# 02_-_SCHEMATIC.net
KiCad netlist of a schematic drawn in Altium Designer
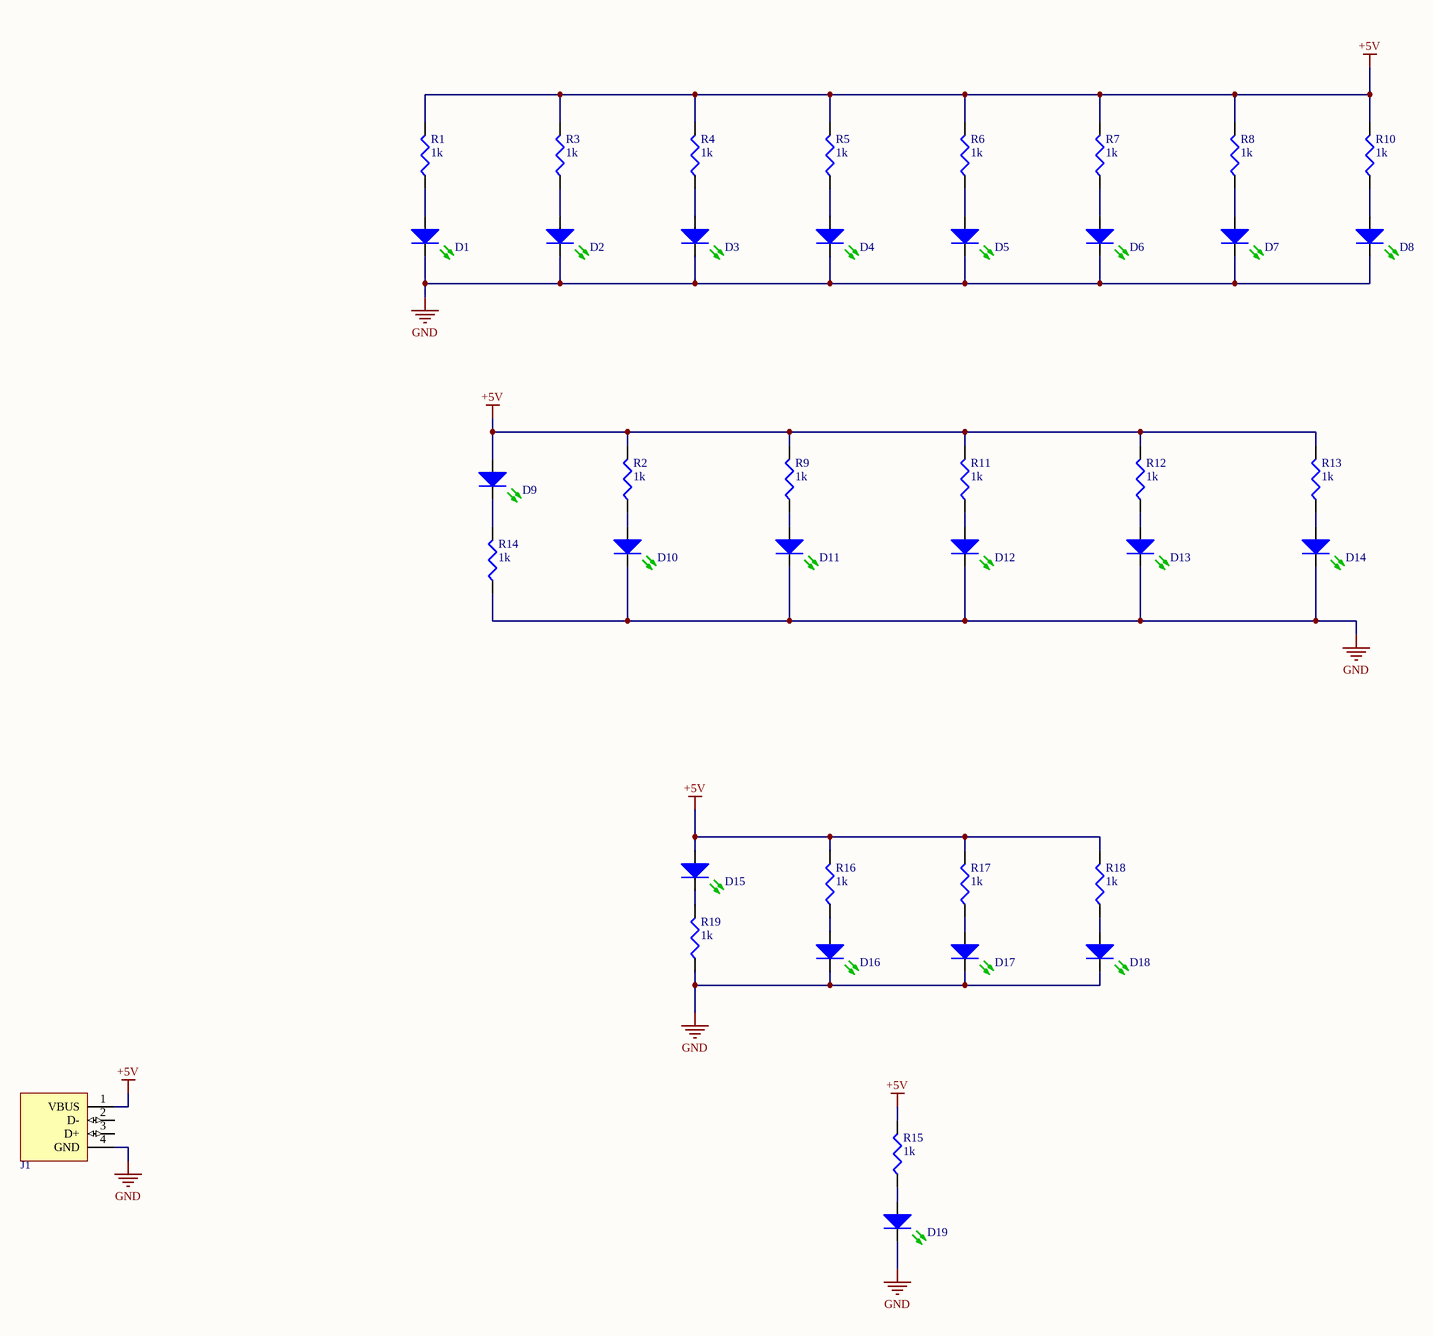
[diagram p0: [02] - SCHEMATIC.SchDoc]

(export (version "E")
  (design (tool "Eeschema 10.0.6"))
  (components
    (comp (ref "D1")
      (value "FYL-3014PGC1A")
      (footprint "LED_THT_Type_3mm_GREEN")
      (description "LED, THT 3mm, Green")
      (fields (field (name "MANUFACTURER") "FORYARD"))
      (libsource (lib "psblib") (part "LED_GREEN_THT_3MM"))
    )
    (comp (ref "D2")
      (value "FYL-3014PGC1A")
      (footprint "LED_THT_Type_3mm_GREEN")
      (description "LED, THT 3mm, Green")
      (fields (field (name "MANUFACTURER") "FORYARD"))
      (libsource (lib "psblib") (part "LED_GREEN_THT_3MM"))
    )
    (comp (ref "D3")
      (value "FYL-3014PGC1A")
      (footprint "LED_THT_Type_3mm_GREEN")
      (description "LED, THT 3mm, Green")
      (fields (field (name "MANUFACTURER") "FORYARD"))
      (libsource (lib "psblib") (part "LED_GREEN_THT_3MM"))
    )
    (comp (ref "D4")
      (value "FYL-3014PGC1A")
      (footprint "LED_THT_Type_3mm_GREEN")
      (description "LED, THT 3mm, Green")
      (fields (field (name "MANUFACTURER") "FORYARD"))
      (libsource (lib "psblib") (part "LED_GREEN_THT_3MM"))
    )
    (comp (ref "D5")
      (value "FYL-3014PGC1A")
      (footprint "LED_THT_Type_3mm_GREEN")
      (description "LED, THT 3mm, Green")
      (fields (field (name "MANUFACTURER") "FORYARD"))
      (libsource (lib "psblib") (part "LED_GREEN_THT_3MM"))
    )
    (comp (ref "D6")
      (value "FYL-3014PGC1A")
      (footprint "LED_THT_Type_3mm_GREEN")
      (description "LED, THT 3mm, Green")
      (fields (field (name "MANUFACTURER") "FORYARD"))
      (libsource (lib "psblib") (part "LED_GREEN_THT_3MM"))
    )
    (comp (ref "D7")
      (value "FYL-3014PGC1A")
      (footprint "LED_THT_Type_3mm_GREEN")
      (description "LED, THT 3mm, Green")
      (fields (field (name "MANUFACTURER") "FORYARD"))
      (libsource (lib "psblib") (part "LED_GREEN_THT_3MM"))
    )
    (comp (ref "D8")
      (value "FYL-3014PGC1A")
      (footprint "LED_THT_Type_3mm_GREEN")
      (description "LED, THT 3mm, Green")
      (fields (field (name "MANUFACTURER") "FORYARD"))
      (libsource (lib "psblib") (part "LED_GREEN_THT_3MM"))
    )
    (comp (ref "D9")
      (value "FYL-3014PGC1A")
      (footprint "LED_THT_Type_3mm_GREEN")
      (description "LED, THT 3mm, Green")
      (fields (field (name "MANUFACTURER") "FORYARD"))
      (libsource (lib "psblib") (part "LED_GREEN_THT_3MM"))
    )
    (comp (ref "D10")
      (value "FYL-3014PGC1A")
      (footprint "LED_THT_Type_3mm_GREEN")
      (description "LED, THT 3mm, Green")
      (fields (field (name "MANUFACTURER") "FORYARD"))
      (libsource (lib "psblib") (part "LED_GREEN_THT_3MM"))
    )
    (comp (ref "D11")
      (value "FYL-3014PGC1A")
      (footprint "LED_THT_Type_3mm_GREEN")
      (description "LED, THT 3mm, Green")
      (fields (field (name "MANUFACTURER") "FORYARD"))
      (libsource (lib "psblib") (part "LED_GREEN_THT_3MM"))
    )
    (comp (ref "D12")
      (value "FYL-3014PGC1A")
      (footprint "LED_THT_Type_3mm_GREEN")
      (description "LED, THT 3mm, Green")
      (fields (field (name "MANUFACTURER") "FORYARD"))
      (libsource (lib "psblib") (part "LED_GREEN_THT_3MM"))
    )
    (comp (ref "D13")
      (value "FYL-3014PGC1A")
      (footprint "LED_THT_Type_3mm_GREEN")
      (description "LED, THT 3mm, Green")
      (fields (field (name "MANUFACTURER") "FORYARD"))
      (libsource (lib "psblib") (part "LED_GREEN_THT_3MM"))
    )
    (comp (ref "D14")
      (value "FYL-3014PGC1A")
      (footprint "LED_THT_Type_3mm_GREEN")
      (description "LED, THT 3mm, Green")
      (fields (field (name "MANUFACTURER") "FORYARD"))
      (libsource (lib "psblib") (part "LED_GREEN_THT_3MM"))
    )
    (comp (ref "D15")
      (value "FYL-3014PGC1A")
      (footprint "LED_THT_Type_3mm_GREEN")
      (description "LED, THT 3mm, Green")
      (fields (field (name "MANUFACTURER") "FORYARD"))
      (libsource (lib "psblib") (part "LED_GREEN_THT_3MM"))
    )
    (comp (ref "D16")
      (value "FYL-3014PGC1A")
      (footprint "LED_THT_Type_3mm_GREEN")
      (description "LED, THT 3mm, Green")
      (fields (field (name "MANUFACTURER") "FORYARD"))
      (libsource (lib "psblib") (part "LED_GREEN_THT_3MM"))
    )
    (comp (ref "D17")
      (value "FYL-3014PGC1A")
      (footprint "LED_THT_Type_3mm_GREEN")
      (description "LED, THT 3mm, Green")
      (fields (field (name "MANUFACTURER") "FORYARD"))
      (libsource (lib "psblib") (part "LED_GREEN_THT_3MM"))
    )
    (comp (ref "D18")
      (value "FYL-3014PGC1A")
      (footprint "LED_THT_Type_3mm_GREEN")
      (description "LED, THT 3mm, Green")
      (fields (field (name "MANUFACTURER") "FORYARD"))
      (libsource (lib "psblib") (part "LED_GREEN_THT_3MM"))
    )
    (comp (ref "D19")
      (value "FYL-3014PGC1A")
      (footprint "LED_THT_Type_3mm_GREEN")
      (description "LED, THT 3mm, Green")
      (fields (field (name "MANUFACTURER") "FORYARD"))
      (libsource (lib "psblib") (part "LED_GREEN_THT_3MM"))
    )
    (comp (ref "J1")
      (value "USB_A_PCB")
      (footprint "USB-A-PCB")
      (description "USB A PCB Edge connector")
      (libsource (lib "psblib") (part "USB_A_PCB"))
    )
    (comp (ref "R1")
      (value "1k")
      (footprint "R0603")
      (description "RES, 1k, 1%, 0.063 W, 0603")
      (fields
        (field (name "TOLERANCE") "±1%")
        (field (name ".CHECKED PCB") "OK RF")
        (field (name ".CHECKED SCH") "RF")
      )
      (libsource (lib "psblib") (part "R0603-1k"))
    )
    (comp (ref "R2")
      (value "1k")
      (footprint "R0603")
      (description "RES, 1k, 1%, 0.063 W, 0603")
      (fields
        (field (name "TOLERANCE") "±1%")
        (field (name ".CHECKED PCB") "OK RF")
        (field (name ".CHECKED SCH") "RF")
      )
      (libsource (lib "psblib") (part "R0603-1k"))
    )
    (comp (ref "R3")
      (value "1k")
      (footprint "R0603")
      (description "RES, 1k, 1%, 0.063 W, 0603")
      (fields
        (field (name "TOLERANCE") "±1%")
        (field (name ".CHECKED PCB") "OK RF")
        (field (name ".CHECKED SCH") "RF")
      )
      (libsource (lib "psblib") (part "R0603-1k"))
    )
    (comp (ref "R4")
      (value "1k")
      (footprint "R0603")
      (description "RES, 1k, 1%, 0.063 W, 0603")
      (fields
        (field (name "TOLERANCE") "±1%")
        (field (name ".CHECKED PCB") "OK RF")
        (field (name ".CHECKED SCH") "RF")
      )
      (libsource (lib "psblib") (part "R0603-1k"))
    )
    (comp (ref "R5")
      (value "1k")
      (footprint "R0603")
      (description "RES, 1k, 1%, 0.063 W, 0603")
      (fields
        (field (name "TOLERANCE") "±1%")
        (field (name ".CHECKED PCB") "OK RF")
        (field (name ".CHECKED SCH") "RF")
      )
      (libsource (lib "psblib") (part "R0603-1k"))
    )
    (comp (ref "R6")
      (value "1k")
      (footprint "R0603")
      (description "RES, 1k, 1%, 0.063 W, 0603")
      (fields
        (field (name "TOLERANCE") "±1%")
        (field (name ".CHECKED PCB") "OK RF")
        (field (name ".CHECKED SCH") "RF")
      )
      (libsource (lib "psblib") (part "R0603-1k"))
    )
    (comp (ref "R7")
      (value "1k")
      (footprint "R0603")
      (description "RES, 1k, 1%, 0.063 W, 0603")
      (fields
        (field (name "TOLERANCE") "±1%")
        (field (name ".CHECKED PCB") "OK RF")
        (field (name ".CHECKED SCH") "RF")
      )
      (libsource (lib "psblib") (part "R0603-1k"))
    )
    (comp (ref "R8")
      (value "1k")
      (footprint "R0603")
      (description "RES, 1k, 1%, 0.063 W, 0603")
      (fields
        (field (name "TOLERANCE") "±1%")
        (field (name ".CHECKED PCB") "OK RF")
        (field (name ".CHECKED SCH") "RF")
      )
      (libsource (lib "psblib") (part "R0603-1k"))
    )
    (comp (ref "R9")
      (value "1k")
      (footprint "R0603")
      (description "RES, 1k, 1%, 0.063 W, 0603")
      (fields
        (field (name "TOLERANCE") "±1%")
        (field (name ".CHECKED PCB") "OK RF")
        (field (name ".CHECKED SCH") "RF")
      )
      (libsource (lib "psblib") (part "R0603-1k"))
    )
    (comp (ref "R10")
      (value "1k")
      (footprint "R0603")
      (description "RES, 1k, 1%, 0.063 W, 0603")
      (fields
        (field (name "TOLERANCE") "±1%")
        (field (name ".CHECKED PCB") "OK RF")
        (field (name ".CHECKED SCH") "RF")
      )
      (libsource (lib "psblib") (part "R0603-1k"))
    )
    (comp (ref "R11")
      (value "1k")
      (footprint "R0603")
      (description "RES, 1k, 1%, 0.063 W, 0603")
      (fields
        (field (name "TOLERANCE") "±1%")
        (field (name ".CHECKED PCB") "OK RF")
        (field (name ".CHECKED SCH") "RF")
      )
      (libsource (lib "psblib") (part "R0603-1k"))
    )
    (comp (ref "R12")
      (value "1k")
      (footprint "R0603")
      (description "RES, 1k, 1%, 0.063 W, 0603")
      (fields
        (field (name "TOLERANCE") "±1%")
        (field (name ".CHECKED PCB") "OK RF")
        (field (name ".CHECKED SCH") "RF")
      )
      (libsource (lib "psblib") (part "R0603-1k"))
    )
    (comp (ref "R13")
      (value "1k")
      (footprint "R0603")
      (description "RES, 1k, 1%, 0.063 W, 0603")
      (fields
        (field (name "TOLERANCE") "±1%")
        (field (name ".CHECKED PCB") "OK RF")
        (field (name ".CHECKED SCH") "RF")
      )
      (libsource (lib "psblib") (part "R0603-1k"))
    )
    (comp (ref "R14")
      (value "1k")
      (footprint "R0603")
      (description "RES, 1k, 1%, 0.063 W, 0603")
      (fields
        (field (name "TOLERANCE") "±1%")
        (field (name ".CHECKED PCB") "OK RF")
        (field (name ".CHECKED SCH") "RF")
      )
      (libsource (lib "psblib") (part "R0603-1k"))
    )
    (comp (ref "R15")
      (value "1k")
      (footprint "R0603")
      (description "RES, 1k, 1%, 0.063 W, 0603")
      (fields
        (field (name "TOLERANCE") "±1%")
        (field (name ".CHECKED PCB") "OK RF")
        (field (name ".CHECKED SCH") "RF")
      )
      (libsource (lib "psblib") (part "R0603-1k"))
    )
    (comp (ref "R16")
      (value "1k")
      (footprint "R0603")
      (description "RES, 1k, 1%, 0.063 W, 0603")
      (fields
        (field (name "TOLERANCE") "±1%")
        (field (name ".CHECKED PCB") "OK RF")
        (field (name ".CHECKED SCH") "RF")
      )
      (libsource (lib "psblib") (part "R0603-1k"))
    )
    (comp (ref "R17")
      (value "1k")
      (footprint "R0603")
      (description "RES, 1k, 1%, 0.063 W, 0603")
      (fields
        (field (name "TOLERANCE") "±1%")
        (field (name ".CHECKED PCB") "OK RF")
        (field (name ".CHECKED SCH") "RF")
      )
      (libsource (lib "psblib") (part "R0603-1k"))
    )
    (comp (ref "R18")
      (value "1k")
      (footprint "R0603")
      (description "RES, 1k, 1%, 0.063 W, 0603")
      (fields
        (field (name "TOLERANCE") "±1%")
        (field (name ".CHECKED PCB") "OK RF")
        (field (name ".CHECKED SCH") "RF")
      )
      (libsource (lib "psblib") (part "R0603-1k"))
    )
    (comp (ref "R19")
      (value "1k")
      (footprint "R0603")
      (description "RES, 1k, 1%, 0.063 W, 0603")
      (fields
        (field (name "TOLERANCE") "±1%")
        (field (name ".CHECKED PCB") "OK RF")
        (field (name ".CHECKED SCH") "RF")
      )
      (libsource (lib "psblib") (part "R0603-1k"))
    )
  )
  (nets
    (net (code "1") (name "+5V") (class "Default")
      (node (ref "D15") (pin "2") (pinfunction "A_2") (pintype "passive"))
      (node (ref "D9") (pin "2") (pinfunction "A_2") (pintype "passive"))
      (node (ref "J1") (pin "1") (pinfunction "VBUS_1") (pintype "power_in"))
      (node (ref "R1") (pin "2") (pinfunction "2_2") (pintype "passive"))
      (node (ref "R10") (pin "2") (pinfunction "2_2") (pintype "passive"))
      (node (ref "R11") (pin "2") (pinfunction "2_2") (pintype "passive"))
      (node (ref "R12") (pin "2") (pinfunction "2_2") (pintype "passive"))
      (node (ref "R13") (pin "2") (pinfunction "2_2") (pintype "passive"))
      (node (ref "R15") (pin "2") (pinfunction "2_2") (pintype "passive"))
      (node (ref "R16") (pin "2") (pinfunction "2_2") (pintype "passive"))
      (node (ref "R17") (pin "2") (pinfunction "2_2") (pintype "passive"))
      (node (ref "R18") (pin "2") (pinfunction "2_2") (pintype "passive"))
      (node (ref "R2") (pin "2") (pinfunction "2_2") (pintype "passive"))
      (node (ref "R3") (pin "2") (pinfunction "2_2") (pintype "passive"))
      (node (ref "R4") (pin "2") (pinfunction "2_2") (pintype "passive"))
      (node (ref "R5") (pin "2") (pinfunction "2_2") (pintype "passive"))
      (node (ref "R6") (pin "2") (pinfunction "2_2") (pintype "passive"))
      (node (ref "R7") (pin "2") (pinfunction "2_2") (pintype "passive"))
      (node (ref "R8") (pin "2") (pinfunction "2_2") (pintype "passive"))
      (node (ref "R9") (pin "2") (pinfunction "2_2") (pintype "passive"))
    )
    (net (code "2") (name "GND") (class "Default")
      (node (ref "D1") (pin "1") (pinfunction "K_1") (pintype "passive"))
      (node (ref "D10") (pin "1") (pinfunction "K_1") (pintype "passive"))
      (node (ref "D11") (pin "1") (pinfunction "K_1") (pintype "passive"))
      (node (ref "D12") (pin "1") (pinfunction "K_1") (pintype "passive"))
      (node (ref "D13") (pin "1") (pinfunction "K_1") (pintype "passive"))
      (node (ref "D14") (pin "1") (pinfunction "K_1") (pintype "passive"))
      (node (ref "D16") (pin "1") (pinfunction "K_1") (pintype "passive"))
      (node (ref "D17") (pin "1") (pinfunction "K_1") (pintype "passive"))
      (node (ref "D18") (pin "1") (pinfunction "K_1") (pintype "passive"))
      (node (ref "D19") (pin "1") (pinfunction "K_1") (pintype "passive"))
      (node (ref "D2") (pin "1") (pinfunction "K_1") (pintype "passive"))
      (node (ref "D3") (pin "1") (pinfunction "K_1") (pintype "passive"))
      (node (ref "D4") (pin "1") (pinfunction "K_1") (pintype "passive"))
      (node (ref "D5") (pin "1") (pinfunction "K_1") (pintype "passive"))
      (node (ref "D6") (pin "1") (pinfunction "K_1") (pintype "passive"))
      (node (ref "D7") (pin "1") (pinfunction "K_1") (pintype "passive"))
      (node (ref "D8") (pin "1") (pinfunction "K_1") (pintype "passive"))
      (node (ref "J1") (pin "4") (pinfunction "GND_4") (pintype "power_in"))
      (node (ref "R14") (pin "1") (pinfunction "1_1") (pintype "passive"))
      (node (ref "R19") (pin "1") (pinfunction "1_1") (pintype "passive"))
    )
    (net (code "3") (name "Net-(D1-A)") (class "Default")
      (node (ref "D1") (pin "2") (pinfunction "A_2") (pintype "passive"))
      (node (ref "R1") (pin "1") (pinfunction "1_1") (pintype "passive"))
    )
    (net (code "4") (name "Net-(D2-A)") (class "Default")
      (node (ref "D2") (pin "2") (pinfunction "A_2") (pintype "passive"))
      (node (ref "R3") (pin "1") (pinfunction "1_1") (pintype "passive"))
    )
    (net (code "5") (name "Net-(D3-A)") (class "Default")
      (node (ref "D3") (pin "2") (pinfunction "A_2") (pintype "passive"))
      (node (ref "R4") (pin "1") (pinfunction "1_1") (pintype "passive"))
    )
    (net (code "6") (name "Net-(D4-A)") (class "Default")
      (node (ref "D4") (pin "2") (pinfunction "A_2") (pintype "passive"))
      (node (ref "R5") (pin "1") (pinfunction "1_1") (pintype "passive"))
    )
    (net (code "7") (name "Net-(D5-A)") (class "Default")
      (node (ref "D5") (pin "2") (pinfunction "A_2") (pintype "passive"))
      (node (ref "R6") (pin "1") (pinfunction "1_1") (pintype "passive"))
    )
    (net (code "8") (name "Net-(D6-A)") (class "Default")
      (node (ref "D6") (pin "2") (pinfunction "A_2") (pintype "passive"))
      (node (ref "R7") (pin "1") (pinfunction "1_1") (pintype "passive"))
    )
    (net (code "9") (name "Net-(D7-A)") (class "Default")
      (node (ref "D7") (pin "2") (pinfunction "A_2") (pintype "passive"))
      (node (ref "R8") (pin "1") (pinfunction "1_1") (pintype "passive"))
    )
    (net (code "10") (name "Net-(D8-A)") (class "Default")
      (node (ref "D8") (pin "2") (pinfunction "A_2") (pintype "passive"))
      (node (ref "R10") (pin "1") (pinfunction "1_1") (pintype "passive"))
    )
    (net (code "11") (name "Net-(D9-K)") (class "Default")
      (node (ref "D9") (pin "1") (pinfunction "K_1") (pintype "passive"))
      (node (ref "R14") (pin "2") (pinfunction "2_2") (pintype "passive"))
    )
    (net (code "12") (name "Net-(D10-A)") (class "Default")
      (node (ref "D10") (pin "2") (pinfunction "A_2") (pintype "passive"))
      (node (ref "R2") (pin "1") (pinfunction "1_1") (pintype "passive"))
    )
    (net (code "13") (name "Net-(D11-A)") (class "Default")
      (node (ref "D11") (pin "2") (pinfunction "A_2") (pintype "passive"))
      (node (ref "R9") (pin "1") (pinfunction "1_1") (pintype "passive"))
    )
    (net (code "14") (name "Net-(D12-A)") (class "Default")
      (node (ref "D12") (pin "2") (pinfunction "A_2") (pintype "passive"))
      (node (ref "R11") (pin "1") (pinfunction "1_1") (pintype "passive"))
    )
    (net (code "15") (name "Net-(D13-A)") (class "Default")
      (node (ref "D13") (pin "2") (pinfunction "A_2") (pintype "passive"))
      (node (ref "R12") (pin "1") (pinfunction "1_1") (pintype "passive"))
    )
    (net (code "16") (name "Net-(D14-A)") (class "Default")
      (node (ref "D14") (pin "2") (pinfunction "A_2") (pintype "passive"))
      (node (ref "R13") (pin "1") (pinfunction "1_1") (pintype "passive"))
    )
    (net (code "17") (name "Net-(D15-K)") (class "Default")
      (node (ref "D15") (pin "1") (pinfunction "K_1") (pintype "passive"))
      (node (ref "R19") (pin "2") (pinfunction "2_2") (pintype "passive"))
    )
    (net (code "18") (name "Net-(D16-A)") (class "Default")
      (node (ref "D16") (pin "2") (pinfunction "A_2") (pintype "passive"))
      (node (ref "R16") (pin "1") (pinfunction "1_1") (pintype "passive"))
    )
    (net (code "19") (name "Net-(D17-A)") (class "Default")
      (node (ref "D17") (pin "2") (pinfunction "A_2") (pintype "passive"))
      (node (ref "R17") (pin "1") (pinfunction "1_1") (pintype "passive"))
    )
    (net (code "20") (name "Net-(D18-A)") (class "Default")
      (node (ref "D18") (pin "2") (pinfunction "A_2") (pintype "passive"))
      (node (ref "R18") (pin "1") (pinfunction "1_1") (pintype "passive"))
    )
    (net (code "21") (name "Net-(D19-A)") (class "Default")
      (node (ref "D19") (pin "2") (pinfunction "A_2") (pintype "passive"))
      (node (ref "R15") (pin "1") (pinfunction "1_1") (pintype "passive"))
    )
    (net (code "22") (name "unconnected-(J1-D+-Pad3)") (class "Default")
      (node (ref "J1") (pin "3") (pinfunction "D+_3") (pintype "bidirectional"))
    )
    (net (code "23") (name "unconnected-(J1-D--Pad2)") (class "Default")
      (node (ref "J1") (pin "2") (pinfunction "D-_2") (pintype "bidirectional"))
    )
  )
)
